# SCH_card0_2025-07-14.net
KiCad netlist of a schematic drawn in EasyEDA
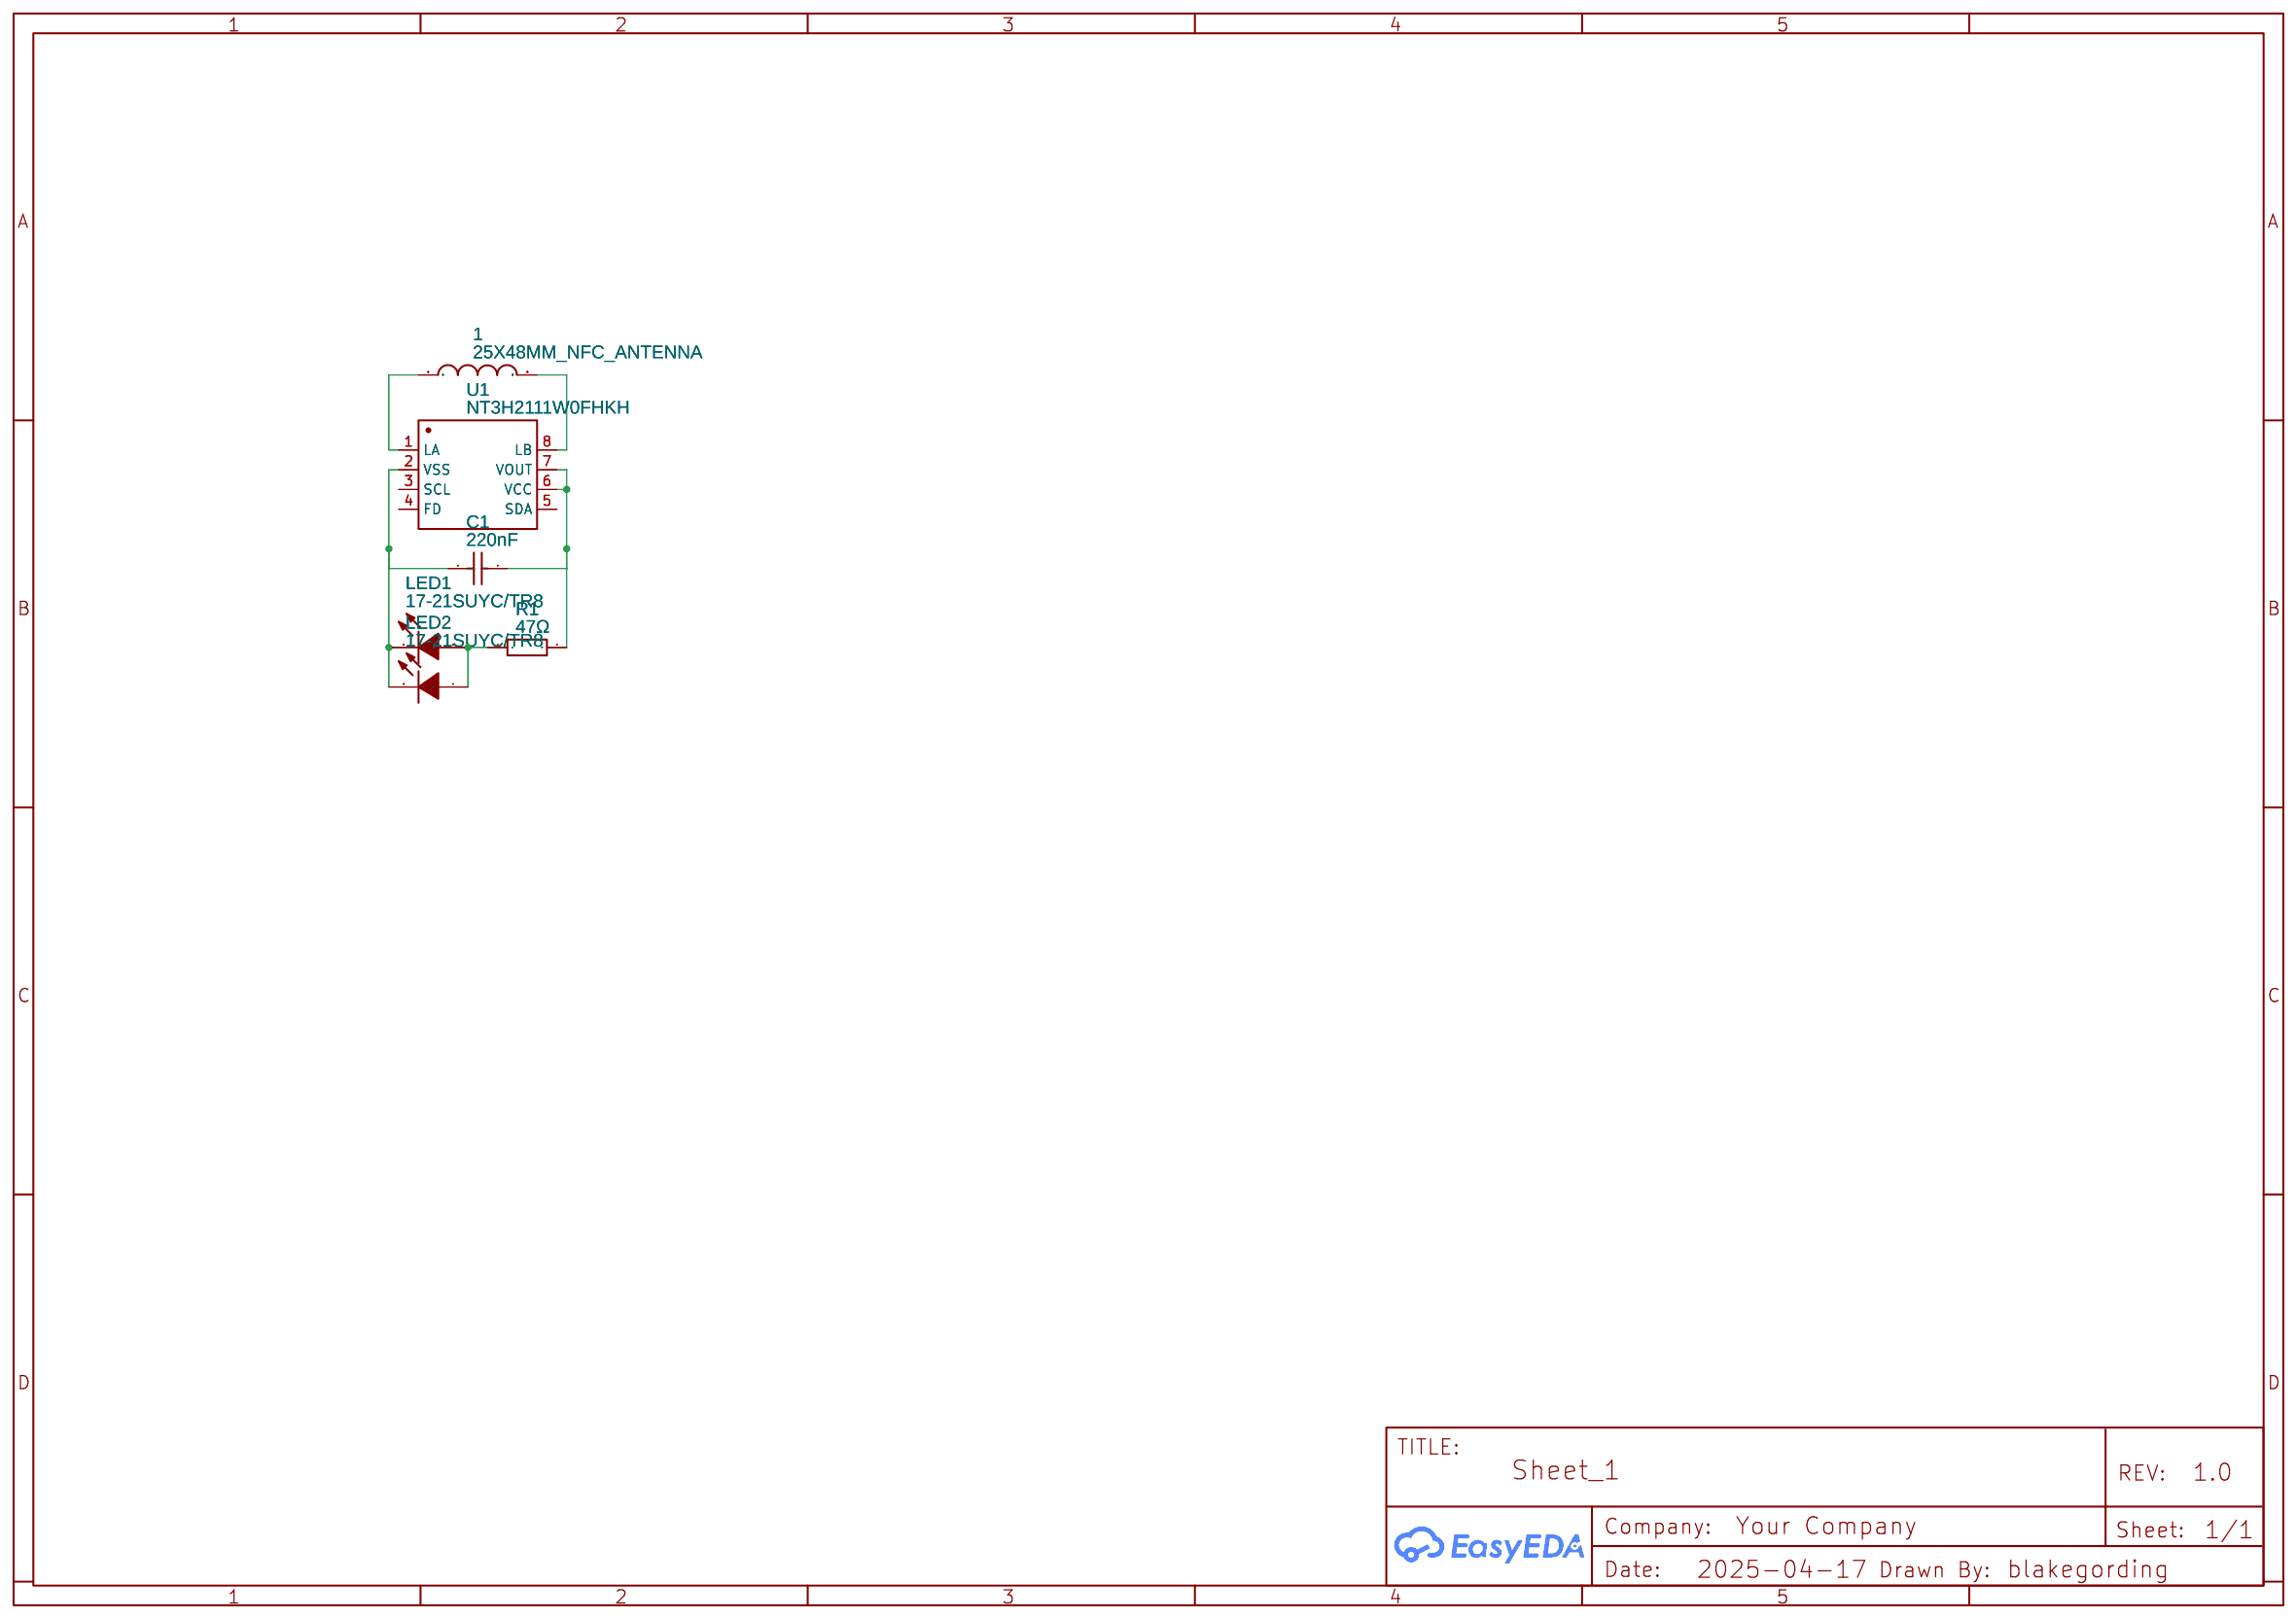
[diagram p0: schematic sheet]

(export (version "E")
  (design (tool "Eeschema 10.0.6"))
  (components
    (comp (ref "1") (value "25X48MM_NFC_ANTENNA") (libsource (lib "") (part "25X48MM_NFC_ANTENNA")))
    (comp (ref "C1")
      (value "220nF")
      (fields
        (field (name "Manufacturer Part") "CL10B224KA8NNNC")
        (field (name "Manufacturer") "SAMSUNG(三星)")
      )
      (libsource (lib "") (part "CL10B224KA8NNNC"))
    )
    (comp (ref "LED1")
      (value "17-21SUYC/TR8")
      (fields (field (name "Manufacturer Part") "KT-0805黄灯") (field (name "Manufacturer") "KENTO"))
      (libsource (lib "") (part "17-21SUYC/TR8"))
    )
    (comp (ref "LED2")
      (value "17-21SUYC/TR8")
      (fields (field (name "Manufacturer Part") "KT-0805黄灯") (field (name "Manufacturer") "KENTO"))
      (libsource (lib "") (part "17-21SUYC/TR8"))
    )
    (comp (ref "R1")
      (value "47Ω")
      (fields
        (field (name "Manufacturer Part") "0603WAF470JT5E")
        (field (name "Manufacturer") "UNI-ROYAL(厚声)")
      )
      (libsource (lib "") (part "0603WAF470JT5E"))
    )
    (comp (ref "U1")
      (value "NT3H2111W0FHKH")
      (fields (field (name "Manufacturer") "NXP(恩智浦)"))
      (libsource (lib "") (part "NT3H2111W0FHKH"))
    )
  )
  (nets
    (net (code "1") (name "Net-(LED1-+)") (class "Default")
      (node (ref "LED1") (pin "1") (pinfunction "+_1") (pintype "unspecified"))
      (node (ref "LED2") (pin "1") (pinfunction "+_1") (pintype "unspecified"))
      (node (ref "R1") (pin "1") (pinfunction "1_1") (pintype "input"))
    )
    (net (code "2") (name "Net-(LED1--)") (class "Default")
      (node (ref "C1") (pin "1") (pinfunction "1_1") (pintype "input"))
      (node (ref "LED1") (pin "2") (pinfunction "-_2") (pintype "unspecified"))
      (node (ref "LED2") (pin "2") (pinfunction "-_2") (pintype "unspecified"))
      (node (ref "U1") (pin "2") (pinfunction "VSS_2") (pintype "unspecified"))
    )
    (net (code "3") (name "Net-(U1-LA)") (class "Default")
      (node (ref "1") (pin "P$1") (pinfunction "P$1_P$1") (pintype "bidirectional"))
      (node (ref "U1") (pin "1") (pinfunction "LA_1") (pintype "unspecified"))
    )
    (net (code "4") (name "Net-(U1-LB)") (class "Default")
      (node (ref "1") (pin "P$2") (pinfunction "P$2_P$2") (pintype "bidirectional"))
      (node (ref "U1") (pin "8") (pinfunction "LB_8") (pintype "unspecified"))
    )
    (net (code "5") (name "Net-(U1-VCC)") (class "Default")
      (node (ref "C1") (pin "2") (pinfunction "2_2") (pintype "input"))
      (node (ref "R1") (pin "2") (pinfunction "2_2") (pintype "input"))
      (node (ref "U1") (pin "6") (pinfunction "VCC_6") (pintype "unspecified"))
      (node (ref "U1") (pin "7") (pinfunction "VOUT_7") (pintype "unspecified"))
    )
    (net (code "6") (name "unconnected-(U1-FD-Pad4)") (class "Default")
      (node (ref "U1") (pin "4") (pinfunction "FD_4") (pintype "unspecified"))
    )
    (net (code "7") (name "unconnected-(U1-SCL-Pad3)") (class "Default")
      (node (ref "U1") (pin "3") (pinfunction "SCL_3") (pintype "unspecified"))
    )
    (net (code "8") (name "unconnected-(U1-SDA-Pad5)") (class "Default")
      (node (ref "U1") (pin "5") (pinfunction "SDA_5") (pintype "unspecified"))
    )
  )
)
